# mach_master3.net
KiCad netlist of a schematic drawn in Altium Designer
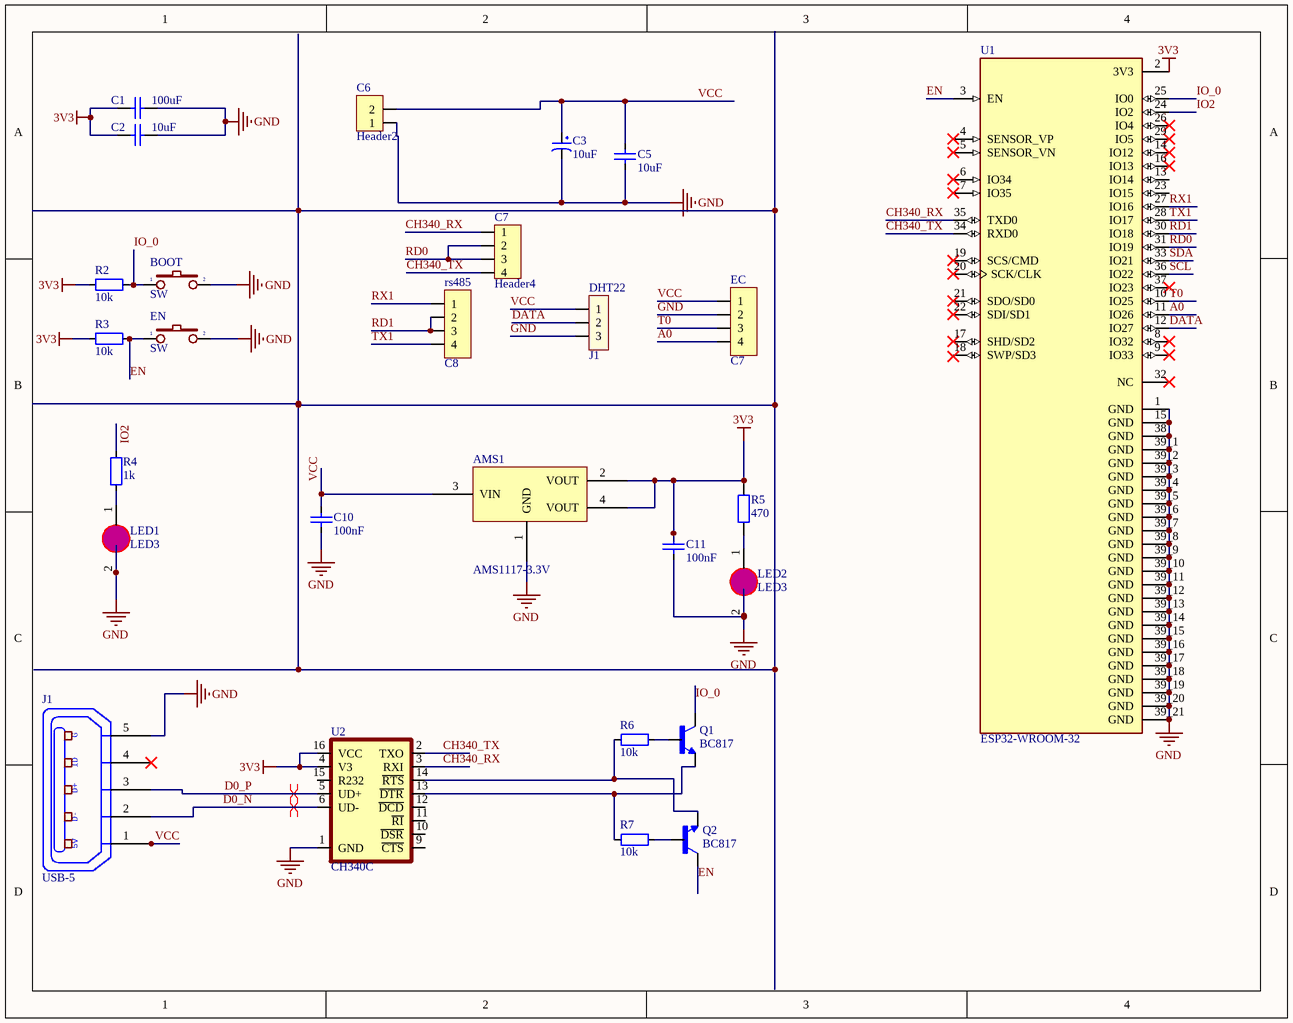
[diagram p0: mach master3.SchDoc]

(export (version "E")
  (design (tool "Eeschema 10.0.6"))
  (components
    (comp (ref "AMS1")
      (value "AMS1117-3.3V")
      (footprint "SOT223")
      (description "Dán")
      (libsource (lib "IC") (part "AMS1117 SMD"))
    )
    (comp (ref "BOOT")
      (value "SW")
      (footprint "SW-SMD")
      (description "Switch button 2 pin")
      (libsource (lib "My Library") (part "SW2"))
    )
    (comp (ref "C1")
      (value "100uF")
      (footprint "CAP_0805")
      (description "Capacitor")
      (fields (field (name "PUBLISHER") "Altium Limited"))
      (libsource (lib "") (part "CapSMD_1"))
    )
    (comp (ref "C2")
      (value "10uF")
      (footprint "CAP_0805")
      (description "Capacitor")
      (fields (field (name "PUBLISHER") "Altium Limited"))
      (libsource (lib "") (part "CapSMD_1"))
    )
    (comp (ref "C3")
      (value "10uF")
      (footprint "tu tantalum smd3216")
      (description "Dán")
      (libsource (lib "Tu dien") (part "Tu tantalum 10uF 16V SMD3216"))
    )
    (comp (ref "C5")
      (value "10uF")
      (footprint "CAP_0805")
      (description "Capacitor")
      (fields (field (name "PUBLISHER") "Altium Limited"))
      (libsource (lib "My Library") (part "CapSMD"))
    )
    (comp (ref "C6")
      (value "Header2")
      (footprint "KF2-5.08")
      (description "Header IDC, 2 x 1 Pin Vertical 2.54mm Pitch (Non-Boxed, Male)")
      (fields
        (field (name "MANUFACTURER") "Würth Elektronik eiSos GmbH")
        (field (name "PARTNO") "613002143121")
        (field (name "CREATED BY") "Karrer Zheng")
      )
      (libsource (lib "My Library") (part "Header2"))
    )
    (comp (ref "C7")
      (value "Header4")
      (footprint "Header4")
      (description "Header IDC, 4 x 1 Pin Vertical 2.54mm Pitch (Non-Boxed, Male)")
      (fields
        (field (name "MANUFACTURER") "Würth Elektronik eiSos GmbH")
        (field (name "PARTNO") "613002143121")
        (field (name "CREATED BY") "Karrer Zheng")
      )
      (libsource (lib "My Library") (part "Header4"))
    )
    (comp (ref "C10")
      (value "100nF")
      (footprint "CAP_0805")
      (description "Capacitor")
      (fields (field (name "PUBLISHER") "Altium Limited"))
      (libsource (lib "My Library") (part "CapSMD"))
    )
    (comp (ref "C11")
      (value "100nF")
      (footprint "CAP_0805")
      (description "Capacitor")
      (fields (field (name "PUBLISHER") "Altium Limited"))
      (libsource (lib "My Library") (part "CapSMD"))
    )
    (comp (ref "DHT22")
      (value "J1")
      (footprint "Header3")
      (description "Jumper 3")
      (libsource (lib "My Library") (part "JP3"))
    )
    (comp (ref "EC")
      (value "C7")
      (footprint "Header4")
      (description "WR-PHD 2.54 mm Angled Socket Header")
      (fields
        (field (name "MANUFACTURER") "Würth Elektronik eiSos GmbH")
        (field (name "PARTNO") "613004143121")
        (field (name "CREATED BY") "Karrer Zheng")
      )
      (libsource (lib "My Library") (part "JP4"))
    )
    (comp (ref "EN")
      (value "SW")
      (footprint "SW-SMD")
      (description "Switch button 2 pin")
      (libsource (lib "My Library") (part "SW2"))
    )
    (comp (ref "J1")
      (value "USB-5")
      (footprint "USB-M1")
      (fields
        (field (name "MANUFACTURER") "FCI")
        (field (name "MANUFACTURER PART NUMBER") "10118193-0001LF")
        (field (name ".CREATOR") "MM")
        (field (name ".CHECKED PCB") "RF")
        (field (name ".CHECKED SCH") "MM")
      )
      (libsource (lib "My Library 2") (part "USB-5"))
    )
    (comp (ref "LED1")
      (value "LED3")
      (footprint "LED0805")
      (description "LED SMD 0805")
      (libsource (lib "My Library 2") (part "LED0805"))
    )
    (comp (ref "LED2")
      (value "LED3")
      (footprint "LED0805")
      (description "LED SMD 0805")
      (libsource (lib "My Library 2") (part "LED0805"))
    )
    (comp (ref "Q1")
      (value "BC817")
      (footprint "SOT95P240X97-3N")
      (description "Bipolar (BJT) Transistor NPN 45V 500mA 100MHz 250mW Surface Mount TO-236AB")
      (fields (field (name "MF") "Rectron"))
      (libsource (lib "") (part "BC817_1"))
    )
    (comp (ref "Q2")
      (value "BC817")
      (footprint "SOT95P240X97-3N")
      (description "Bipolar (BJT) Transistor NPN 45V 500mA 100MHz 250mW Surface Mount TO-236AB")
      (fields (field (name "MF") "Rectron"))
      (libsource (lib "BC817") (part "BC817"))
    )
    (comp (ref "R2")
      (value "10k")
      (footprint "RES-SMD-0805")
      (description "Resistor")
      (fields
        (field (name "MANUFACTURER") "Generic Components")
        (field (name "PUBLISHER") "Altium Hobart Technology Centre")
      )
      (libsource (lib "My Library") (part "Resistor - SMD"))
    )
    (comp (ref "R3")
      (value "10k")
      (footprint "RES-SMD-0805")
      (description "Resistor")
      (fields
        (field (name "MANUFACTURER") "Generic Components")
        (field (name "PUBLISHER") "Altium Hobart Technology Centre")
      )
      (libsource (lib "My Library") (part "Resistor - SMD"))
    )
    (comp (ref "R4")
      (value "1k")
      (footprint "RES-SMD-0805")
      (description "Resistor")
      (fields
        (field (name "MANUFACTURER") "Generic Components")
        (field (name "PUBLISHER") "Altium Hobart Technology Centre")
      )
      (libsource (lib "My Library") (part "Resistor - SMD"))
    )
    (comp (ref "R5")
      (value "470")
      (footprint "RES-SMD-0805")
      (description "22")
      (fields
        (field (name "MANUFACTURER") "Generic Components")
        (field (name "PUBLISHER") "Altium Hobart Technology Centre")
      )
      (libsource (lib "") (part "Resistor - SMD_1"))
    )
    (comp (ref "R6")
      (value "10k")
      (footprint "RES-SMD-0805")
      (description "Resistor")
      (fields
        (field (name "MANUFACTURER") "Generic Components")
        (field (name "PUBLISHER") "Altium Hobart Technology Centre")
      )
      (libsource (lib "My Library") (part "Resistor - SMD"))
    )
    (comp (ref "R7")
      (value "10k")
      (footprint "RES-SMD-0805")
      (description "Resistor")
      (fields
        (field (name "MANUFACTURER") "Generic Components")
        (field (name "PUBLISHER") "Altium Hobart Technology Centre")
      )
      (libsource (lib "My Library") (part "Resistor - SMD"))
    )
    (comp (ref "rs485")
      (value "C8")
      (footprint "Header4")
      (description "WR-PHD 2.54 mm Angled Socket Header")
      (fields
        (field (name "MANUFACTURER") "Würth Elektronik eiSos GmbH")
        (field (name "PARTNO") "613004143121")
        (field (name "CREATED BY") "Karrer Zheng")
      )
      (libsource (lib "My Library") (part "JP4"))
    )
    (comp (ref "U1")
      (value "ESP32-WROOM-32")
      (footprint "MODULE_ESP32-WROOM-32")
      (fields (field (name "MF") "Espressif Systems"))
      (libsource (lib "ESP32-WROOM-32") (part "ESP32-WROOM-32"))
    )
    (comp (ref "U2")
      (value "CH340C")
      (footprint "SOP-16")
      (description "USB to serial chip CH340")
      (fields (field (name "MF") "WCH"))
      (libsource (lib "My Library") (part "CH340C"))
    )
  )
  (nets
    (net (code "1") (name "/A0") (class "Default")
      (node (ref "EC") (pin "4") (pinfunction "4_4") (pintype "passive"))
      (node (ref "U1") (pin "11") (pinfunction "IO26_11") (pintype "bidirectional"))
    )
    (net (code "2") (name "/CH340_RX") (class "Default")
      (node (ref "C7") (pin "1") (pinfunction "1_1") (pintype "passive"))
      (node (ref "U1") (pin "35") (pinfunction "TXD0_35") (pintype "bidirectional"))
      (node (ref "U2") (pin "3") (pinfunction "RXI_3") (pintype "bidirectional"))
    )
    (net (code "3") (name "/CH340_TX") (class "Default")
      (node (ref "C7") (pin "4") (pinfunction "4_4") (pintype "passive"))
      (node (ref "U1") (pin "34") (pinfunction "RXD0_34") (pintype "bidirectional"))
      (node (ref "U2") (pin "2") (pinfunction "TXO_2") (pintype "bidirectional"))
    )
    (net (code "4") (name "/D0_N") (class "Default")
      (node (ref "J1") (pin "2") (pinfunction "P2_2") (pintype "passive"))
      (node (ref "U2") (pin "6") (pinfunction "UD-_6") (pintype "bidirectional"))
    )
    (net (code "5") (name "/D0_P") (class "Default")
      (node (ref "J1") (pin "3") (pinfunction "P3_3") (pintype "passive"))
      (node (ref "U2") (pin "5") (pinfunction "UD+_5") (pintype "bidirectional"))
    )
    (net (code "6") (name "/DATA") (class "Default")
      (node (ref "DHT22") (pin "2") (pinfunction "2_2") (pintype "passive"))
      (node (ref "U1") (pin "12") (pinfunction "IO27_12") (pintype "bidirectional"))
    )
    (net (code "7") (name "/EN") (class "Default")
      (node (ref "EN") (pin "1") (pinfunction "1_1") (pintype "passive"))
      (node (ref "Q2") (pin "3") (pinfunction "C_3") (pintype "passive"))
      (node (ref "R3") (pin "1") (pinfunction "1_1") (pintype "passive"))
      (node (ref "U1") (pin "3") (pinfunction "EN_3") (pintype "input"))
    )
    (net (code "8") (name "/IO2") (class "Default")
      (node (ref "R4") (pin "2") (pinfunction "2_2") (pintype "passive"))
      (node (ref "U1") (pin "24") (pinfunction "IO2_24") (pintype "bidirectional"))
    )
    (net (code "9") (name "/IO_0") (class "Default")
      (node (ref "BOOT") (pin "1") (pinfunction "1_1") (pintype "passive"))
      (node (ref "Q1") (pin "3") (pinfunction "C_3") (pintype "passive"))
      (node (ref "R2") (pin "1") (pinfunction "1_1") (pintype "passive"))
      (node (ref "U1") (pin "25") (pinfunction "IO0_25") (pintype "bidirectional"))
    )
    (net (code "10") (name "/RD0") (class "Default")
      (node (ref "C7") (pin "2") (pinfunction "2_2") (pintype "passive"))
      (node (ref "C7") (pin "3") (pinfunction "3_3") (pintype "passive"))
      (node (ref "U1") (pin "31") (pinfunction "IO19_31") (pintype "bidirectional"))
    )
    (net (code "11") (name "/RD1") (class "Default")
      (node (ref "U1") (pin "30") (pinfunction "IO18_30") (pintype "bidirectional"))
      (node (ref "rs485") (pin "2") (pinfunction "2_2") (pintype "passive"))
      (node (ref "rs485") (pin "3") (pinfunction "3_3") (pintype "passive"))
    )
    (net (code "12") (name "/RX1") (class "Default")
      (node (ref "U1") (pin "27") (pinfunction "IO16_27") (pintype "bidirectional"))
      (node (ref "rs485") (pin "1") (pinfunction "1_1") (pintype "passive"))
    )
    (net (code "13") (name "/SCL") (class "Default")
      (node (ref "U1") (pin "36") (pinfunction "IO22_36") (pintype "bidirectional"))
    )
    (net (code "14") (name "/SDA") (class "Default")
      (node (ref "U1") (pin "33") (pinfunction "IO21_33") (pintype "bidirectional"))
    )
    (net (code "15") (name "/T0") (class "Default")
      (node (ref "EC") (pin "3") (pinfunction "3_3") (pintype "passive"))
      (node (ref "U1") (pin "10") (pinfunction "IO25_10") (pintype "bidirectional"))
    )
    (net (code "16") (name "/TX1") (class "Default")
      (node (ref "U1") (pin "28") (pinfunction "IO17_28") (pintype "bidirectional"))
      (node (ref "rs485") (pin "4") (pinfunction "4_4") (pintype "passive"))
    )
    (net (code "17") (name "/VCC") (class "Default")
      (node (ref "AMS1") (pin "3") (pinfunction "VIN_3") (pintype "passive"))
      (node (ref "C10") (pin "2") (pinfunction "2_2") (pintype "passive"))
      (node (ref "C3") (pin "1") (pinfunction "1_1") (pintype "passive"))
      (node (ref "C5") (pin "2") (pinfunction "2_2") (pintype "passive"))
      (node (ref "C6") (pin "2") (pinfunction "2_2") (pintype "passive"))
      (node (ref "DHT22") (pin "1") (pinfunction "1_1") (pintype "passive"))
      (node (ref "EC") (pin "1") (pinfunction "1_1") (pintype "passive"))
      (node (ref "J1") (pin "1") (pinfunction "P1_1") (pintype "passive"))
    )
    (net (code "18") (name "3V3") (class "Default")
      (node (ref "AMS1") (pin "2") (pinfunction "VOUT_2") (pintype "passive"))
      (node (ref "AMS1") (pin "4") (pinfunction "VOUT_4") (pintype "passive"))
      (node (ref "C1") (pin "1") (pinfunction "1_1") (pintype "passive"))
      (node (ref "C11") (pin "2") (pinfunction "2_2") (pintype "passive"))
      (node (ref "C2") (pin "1") (pinfunction "1_1") (pintype "passive"))
      (node (ref "R2") (pin "2") (pinfunction "2_2") (pintype "passive"))
      (node (ref "R3") (pin "2") (pinfunction "2_2") (pintype "passive"))
      (node (ref "R5") (pin "1") (pinfunction "1_1") (pintype "passive"))
      (node (ref "U1") (pin "2") (pinfunction "3V3_2") (pintype "power_in"))
      (node (ref "U2") (pin "16") (pinfunction "VCC_16") (pintype "bidirectional"))
      (node (ref "U2") (pin "4") (pinfunction "V3_4") (pintype "bidirectional"))
    )
    (net (code "19") (name "GND") (class "Default")
      (node (ref "AMS1") (pin "1") (pinfunction "GND_1") (pintype "passive"))
      (node (ref "BOOT") (pin "2") (pinfunction "2_2") (pintype "passive"))
      (node (ref "C1") (pin "2") (pinfunction "2_2") (pintype "passive"))
      (node (ref "C10") (pin "1") (pinfunction "1_1") (pintype "passive"))
      (node (ref "C11") (pin "1") (pinfunction "1_1") (pintype "passive"))
      (node (ref "C2") (pin "2") (pinfunction "2_2") (pintype "passive"))
      (node (ref "C3") (pin "2") (pinfunction "2_2") (pintype "passive"))
      (node (ref "C5") (pin "1") (pinfunction "1_1") (pintype "passive"))
      (node (ref "C6") (pin "1") (pinfunction "1_1") (pintype "passive"))
      (node (ref "DHT22") (pin "3") (pinfunction "3_3") (pintype "passive"))
      (node (ref "EC") (pin "2") (pinfunction "2_2") (pintype "passive"))
      (node (ref "EN") (pin "2") (pinfunction "2_2") (pintype "passive"))
      (node (ref "J1") (pin "5") (pinfunction "P5_5") (pintype "passive"))
      (node (ref "LED1") (pin "2") (pinfunction "K_2") (pintype "passive"))
      (node (ref "LED2") (pin "2") (pinfunction "K_2") (pintype "passive"))
      (node (ref "U1") (pin "1") (pinfunction "GND_1") (pintype "power_in"))
      (node (ref "U1") (pin "15") (pinfunction "GND_15") (pintype "power_in"))
      (node (ref "U1") (pin "38") (pinfunction "GND_38") (pintype "power_in"))
      (node (ref "U1") (pin "39_1") (pinfunction "GND_39_1") (pintype "power_in"))
      (node (ref "U1") (pin "39_10") (pinfunction "GND_39_10") (pintype "power_in"))
      (node (ref "U1") (pin "39_11") (pinfunction "GND_39_11") (pintype "power_in"))
      (node (ref "U1") (pin "39_12") (pinfunction "GND_39_12") (pintype "power_in"))
      (node (ref "U1") (pin "39_13") (pinfunction "GND_39_13") (pintype "power_in"))
      (node (ref "U1") (pin "39_14") (pinfunction "GND_39_14") (pintype "power_in"))
      (node (ref "U1") (pin "39_15") (pinfunction "GND_39_15") (pintype "power_in"))
      (node (ref "U1") (pin "39_16") (pinfunction "GND_39_16") (pintype "power_in"))
      (node (ref "U1") (pin "39_17") (pinfunction "GND_39_17") (pintype "power_in"))
      (node (ref "U1") (pin "39_18") (pinfunction "GND_39_18") (pintype "power_in"))
      (node (ref "U1") (pin "39_19") (pinfunction "GND_39_19") (pintype "power_in"))
      (node (ref "U1") (pin "39_2") (pinfunction "GND_39_2") (pintype "power_in"))
      (node (ref "U1") (pin "39_20") (pinfunction "GND_39_20") (pintype "power_in"))
      (node (ref "U1") (pin "39_21") (pinfunction "GND_39_21") (pintype "power_in"))
      (node (ref "U1") (pin "39_3") (pinfunction "GND_39_3") (pintype "power_in"))
      (node (ref "U1") (pin "39_4") (pinfunction "GND_39_4") (pintype "power_in"))
      (node (ref "U1") (pin "39_5") (pinfunction "GND_39_5") (pintype "power_in"))
      (node (ref "U1") (pin "39_6") (pinfunction "GND_39_6") (pintype "power_in"))
      (node (ref "U1") (pin "39_7") (pinfunction "GND_39_7") (pintype "power_in"))
      (node (ref "U1") (pin "39_8") (pinfunction "GND_39_8") (pintype "power_in"))
      (node (ref "U1") (pin "39_9") (pinfunction "GND_39_9") (pintype "power_in"))
      (node (ref "U2") (pin "1") (pinfunction "GND_1") (pintype "bidirectional"))
    )
    (net (code "20") (name "Net-(LED1-A)") (class "Default")
      (node (ref "LED1") (pin "1") (pinfunction "A_1") (pintype "passive"))
      (node (ref "R4") (pin "1") (pinfunction "1_1") (pintype "passive"))
    )
    (net (code "21") (name "Net-(LED2-A)") (class "Default")
      (node (ref "LED2") (pin "1") (pinfunction "A_1") (pintype "passive"))
      (node (ref "R5") (pin "2") (pinfunction "2_2") (pintype "passive"))
    )
    (net (code "22") (name "Net-(Q1-B)") (class "Default")
      (node (ref "Q1") (pin "1") (pinfunction "B_1") (pintype "passive"))
      (node (ref "R6") (pin "1") (pinfunction "1_1") (pintype "passive"))
    )
    (net (code "23") (name "Net-(Q1-E)") (class "Default")
      (node (ref "Q1") (pin "2") (pinfunction "E_2") (pintype "passive"))
      (node (ref "R7") (pin "2") (pinfunction "2_2") (pintype "passive"))
      (node (ref "U2") (pin "13") (pinfunction "~{DTR}_13") (pintype "bidirectional"))
    )
    (net (code "24") (name "Net-(Q2-B)") (class "Default")
      (node (ref "Q2") (pin "1") (pinfunction "B_1") (pintype "passive"))
      (node (ref "R7") (pin "1") (pinfunction "1_1") (pintype "passive"))
    )
    (net (code "25") (name "Net-(Q2-E)") (class "Default")
      (node (ref "Q2") (pin "2") (pinfunction "E_2") (pintype "passive"))
      (node (ref "R6") (pin "2") (pinfunction "2_2") (pintype "passive"))
      (node (ref "U2") (pin "14") (pinfunction "~{RTS}_14") (pintype "bidirectional"))
    )
    (net (code "26") (name "unconnected-(J1-P4-Pad4)") (class "Default")
      (node (ref "J1") (pin "4") (pinfunction "P4_4") (pintype "passive+no_connect"))
    )
    (net (code "27") (name "unconnected-(U1-IO4-Pad26)") (class "Default")
      (node (ref "U1") (pin "26") (pinfunction "IO4_26") (pintype "bidirectional+no_connect"))
    )
    (net (code "28") (name "unconnected-(U1-IO5-Pad29)") (class "Default")
      (node (ref "U1") (pin "29") (pinfunction "IO5_29") (pintype "bidirectional+no_connect"))
    )
    (net (code "29") (name "unconnected-(U1-IO12-Pad14)") (class "Default")
      (node (ref "U1") (pin "14") (pinfunction "IO12_14") (pintype "bidirectional+no_connect"))
    )
    (net (code "30") (name "unconnected-(U1-IO13-Pad16)") (class "Default")
      (node (ref "U1") (pin "16") (pinfunction "IO13_16") (pintype "bidirectional+no_connect"))
    )
    (net (code "31") (name "unconnected-(U1-IO14-Pad13)") (class "Default")
      (node (ref "U1") (pin "13") (pinfunction "IO14_13") (pintype "bidirectional"))
    )
    (net (code "32") (name "unconnected-(U1-IO15-Pad23)") (class "Default")
      (node (ref "U1") (pin "23") (pinfunction "IO15_23") (pintype "bidirectional"))
    )
    (net (code "33") (name "unconnected-(U1-IO23-Pad37)") (class "Default")
      (node (ref "U1") (pin "37") (pinfunction "IO23_37") (pintype "bidirectional+no_connect"))
    )
    (net (code "34") (name "unconnected-(U1-IO32-Pad8)") (class "Default")
      (node (ref "U1") (pin "8") (pinfunction "IO32_8") (pintype "bidirectional+no_connect"))
    )
    (net (code "35") (name "unconnected-(U1-IO33-Pad9)") (class "Default")
      (node (ref "U1") (pin "9") (pinfunction "IO33_9") (pintype "bidirectional+no_connect"))
    )
    (net (code "36") (name "unconnected-(U1-IO34-Pad6)") (class "Default")
      (node (ref "U1") (pin "6") (pinfunction "IO34_6") (pintype "input+no_connect"))
    )
    (net (code "37") (name "unconnected-(U1-IO35-Pad7)") (class "Default")
      (node (ref "U1") (pin "7") (pinfunction "IO35_7") (pintype "input+no_connect"))
    )
    (net (code "38") (name "unconnected-(U1-NC-Pad32)") (class "Default")
      (node (ref "U1") (pin "32") (pinfunction "NC_32") (pintype "passive+no_connect"))
    )
    (net (code "39") (name "unconnected-(U1-SCK{slash}CLK-Pad20)") (class "Default")
      (node (ref "U1") (pin "20") (pinfunction "SCK/CLK_20") (pintype "bidirectional+no_connect"))
    )
    (net (code "40") (name "unconnected-(U1-SCS{slash}CMD-Pad19)") (class "Default")
      (node (ref "U1") (pin "19") (pinfunction "SCS/CMD_19") (pintype "bidirectional+no_connect"))
    )
    (net (code "41") (name "unconnected-(U1-SDI{slash}SD1-Pad22)") (class "Default")
      (node (ref "U1") (pin "22") (pinfunction "SDI/SD1_22") (pintype "bidirectional+no_connect"))
    )
    (net (code "42") (name "unconnected-(U1-SDO{slash}SD0-Pad21)") (class "Default")
      (node (ref "U1") (pin "21") (pinfunction "SDO/SD0_21") (pintype "bidirectional+no_connect"))
    )
    (net (code "43") (name "unconnected-(U1-SENSOR_VN-Pad5)") (class "Default")
      (node (ref "U1") (pin "5") (pinfunction "SENSOR_VN_5") (pintype "input+no_connect"))
    )
    (net (code "44") (name "unconnected-(U1-SENSOR_VP-Pad4)") (class "Default")
      (node (ref "U1") (pin "4") (pinfunction "SENSOR_VP_4") (pintype "input+no_connect"))
    )
    (net (code "45") (name "unconnected-(U1-SHD{slash}SD2-Pad17)") (class "Default")
      (node (ref "U1") (pin "17") (pinfunction "SHD/SD2_17") (pintype "bidirectional+no_connect"))
    )
    (net (code "46") (name "unconnected-(U1-SWP{slash}SD3-Pad18)") (class "Default")
      (node (ref "U1") (pin "18") (pinfunction "SWP/SD3_18") (pintype "bidirectional"))
    )
    (net (code "47") (name "unconnected-(U2-R232-Pad15)") (class "Default")
      (node (ref "U2") (pin "15") (pinfunction "R232_15") (pintype "bidirectional"))
    )
    (net (code "48") (name "unconnected-(U2-~{CTS}-Pad9)") (class "Default")
      (node (ref "U2") (pin "9") (pinfunction "~{CTS}_9") (pintype "bidirectional"))
    )
    (net (code "49") (name "unconnected-(U2-~{DCD}-Pad12)") (class "Default")
      (node (ref "U2") (pin "12") (pinfunction "~{DCD}_12") (pintype "bidirectional"))
    )
    (net (code "50") (name "unconnected-(U2-~{DSR}-Pad10)") (class "Default")
      (node (ref "U2") (pin "10") (pinfunction "~{DSR}_10") (pintype "bidirectional"))
    )
    (net (code "51") (name "unconnected-(U2-~{RI}-Pad11)") (class "Default")
      (node (ref "U2") (pin "11") (pinfunction "~{RI}_11") (pintype "bidirectional"))
    )
  )
)
